# LCD-43.net
KiCad netlist of a schematic drawn in Altium Designer
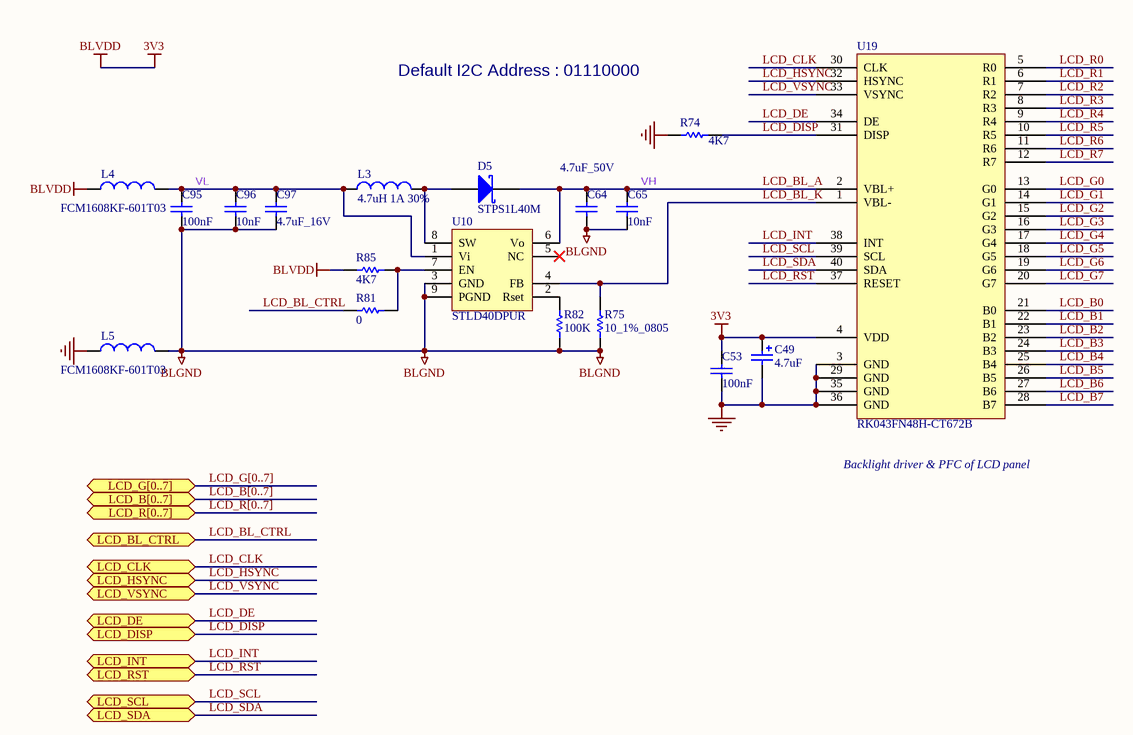
[diagram p0: LCD-43.SchDoc]

(export (version "E")
  (design (tool "Eeschema 10.0.6"))
  (components
    (comp (ref "C49")
      (value "4.7uF")
      (footprint "TAN-A")
      (description "Polarized Capacitor,4.7uF,16V,10%,typeA,AVX")
      (libsource (lib "MCD_TOOLS") (part "Cap_4.7uF_POL_10%_TANA"))
    )
    (comp (ref "C53")
      (value "100nF")
      (footprint "0402C")
      (description "Capacitor,100nF,16V,X7R,10%,0402,YAGEO")
      (libsource (lib "MCD_TOOLS") (part "Cap_100nF_X7R_10%_0402"))
    )
    (comp (ref "C64")
      (value "4.7uF_50V")
      (footprint "1206C")
      (description "Capacitor,4.7uF,50V, X7R,10%,1206,AVX")
      (libsource (lib "MCD_TOOLS") (part "Cap_4.7uF_X7R_10%_1206"))
    )
    (comp (ref "C65")
      (value "10nF")
      (footprint "0603C")
      (description "Capacitor,10nF,50V,X7R,10%,0603,YAGEO")
      (libsource (lib "MCD_TOOLS") (part "Cap_10nF_X7R_10%_0603"))
    )
    (comp (ref "C95")
      (value "100nF")
      (footprint "0603C")
      (description "Capacitor,100nF,16V,X7R,10%,0603,YAGEO")
      (libsource (lib "MCD_TOOLS") (part "Cap_100nF_X7R_10%_0603"))
    )
    (comp (ref "C96")
      (value "10nF")
      (footprint "0603C")
      (description "Capacitor,10nF,50V,X7R,10%,0603,YAGEO")
      (libsource (lib "MCD_TOOLS") (part "Cap_10nF_X7R_10%_0603"))
    )
    (comp (ref "C97")
      (value "4.7uF_16V")
      (footprint "1206C")
      (description "Capacitor,4.7uF,16V, X5R,10%,1206,AVX")
      (libsource (lib "MCD_TOOLS") (part "Cap_4.7uF_X5R_10%_1206"))
    )
    (comp (ref "D5")
      (value "STPS1L40M")
      (footprint "DO216-AA")
      (description "Low Drop power Schottky rectifier(1A, 40V, 0.4V)")
      (libsource (lib "MCD_TOOLS") (part "STPS1L40M"))
    )
    (comp (ref "L3")
      (value "4.7uH 1A 30%")
      (footprint "1210L")
      (description "FIXED IND 4.7UH 1A 180 MOHM 30% SMD")
      (libsource (lib "MCD_TOOLS") (part "Ind_4.7uH_1A_30%"))
    )
    (comp (ref "L4")
      (value "FCM1608KF-601T03")
      (footprint "0603L")
      (description "Bead,600R,350mA,0603,FCM1608KF-601T03,Tai-tech")
      (libsource (lib "MCD_TOOLS") (part "BEAD_600R_350MA_0603"))
    )
    (comp (ref "L5")
      (value "FCM1608KF-601T03")
      (footprint "0603L")
      (description "Bead,600R,350mA,0603,FCM1608KF-601T03,Tai-tech")
      (libsource (lib "MCD_TOOLS") (part "BEAD_600R_350MA_0603"))
    )
    (comp (ref "R74")
      (value "4K7")
      (footprint "0402R")
      (description "Resistor,4K7,0402,1%,YAGEO")
      (libsource (lib "MCD_TOOLS") (part "Res_4K7_1%_0402"))
    )
    (comp (ref "R75")
      (value "10_1%_0805")
      (footprint "0805R")
      (description "Resistor,10,0805,1%,Stackpole,1/4W")
      (libsource (lib "MCD_TOOLS") (part "Res_10_1%_0805"))
    )
    (comp (ref "R81")
      (value "0")
      (footprint "0402R")
      (description "Resistor,0,0402,5%,YAGEO")
      (libsource (lib "MCD_TOOLS") (part "Res_0_5%_0402"))
    )
    (comp (ref "R82")
      (value "100K")
      (footprint "0402R")
      (description "Resistor,100K,0402,1%,YAGEO")
      (libsource (lib "MCD_TOOLS") (part "Res_100K_1%_0402"))
    )
    (comp (ref "R85")
      (value "4K7")
      (footprint "0402R")
      (description "Resistor,4K7,0402,1%,YAGEO")
      (libsource (lib "MCD_TOOLS") (part "Res_4K7_1%_0402"))
    )
    (comp (ref "U10")
      (value "STLD40DPUR")
      (footprint "QFN8_0R65_3X3_ST")
      (description "White LED power supply for large display backlight, QFN8")
      (libsource (lib "MCD_TOOLS") (part "STLD40DPUR"))
    )
    (comp (ref "U19")
      (value "RK043FN48H-CT672B")
      (footprint "RK043FN48H")
      (description "4.3 inch TFT 480*272 pixels with LED Backlight and Capacitive touch panel, high luminance")
      (libsource (lib "MCD_TOOLS") (part "RK043FN48H-CT672B"))
    )
  )
  (nets
    (net (code "1") (name "/LCD_B0") (class "Default")
      (node (ref "U19") (pin "21") (pinfunction "B0_21") (pintype "passive"))
    )
    (net (code "2") (name "/LCD_B1") (class "Default")
      (node (ref "U19") (pin "22") (pinfunction "B1_22") (pintype "passive"))
    )
    (net (code "3") (name "/LCD_B2") (class "Default")
      (node (ref "U19") (pin "23") (pinfunction "B2_23") (pintype "passive"))
    )
    (net (code "4") (name "/LCD_B3") (class "Default")
      (node (ref "U19") (pin "24") (pinfunction "B3_24") (pintype "passive"))
    )
    (net (code "5") (name "/LCD_B4") (class "Default")
      (node (ref "U19") (pin "25") (pinfunction "B4_25") (pintype "passive"))
    )
    (net (code "6") (name "/LCD_B5") (class "Default")
      (node (ref "U19") (pin "26") (pinfunction "B5_26") (pintype "passive"))
    )
    (net (code "7") (name "/LCD_B6") (class "Default")
      (node (ref "U19") (pin "27") (pinfunction "B6_27") (pintype "passive"))
    )
    (net (code "8") (name "/LCD_B7") (class "Default")
      (node (ref "U19") (pin "28") (pinfunction "B7_28") (pintype "passive"))
    )
    (net (code "9") (name "/LCD_BL_A") (class "Default")
      (node (ref "C64") (pin "1") (pinfunction "1_1") (pintype "passive"))
      (node (ref "C65") (pin "2") (pinfunction "2_2") (pintype "passive"))
      (node (ref "D5") (pin "2") (pinfunction "K_2") (pintype "passive"))
      (node (ref "U10") (pin "6") (pinfunction "Vo_6") (pintype "passive"))
      (node (ref "U19") (pin "2") (pinfunction "VBL+_2") (pintype "passive"))
    )
    (net (code "10") (name "/LCD_BL_CTRL") (class "Default")
      (node (ref "R81") (pin "2") (pinfunction "2_2") (pintype "passive"))
    )
    (net (code "11") (name "/LCD_BL_K") (class "Default")
      (node (ref "R75") (pin "2") (pinfunction "2_2") (pintype "passive"))
      (node (ref "U10") (pin "4") (pinfunction "FB_4") (pintype "passive"))
      (node (ref "U19") (pin "1") (pinfunction "VBL-_1") (pintype "passive"))
    )
    (net (code "13") (name "/LCD_CLK") (class "Default")
      (node (ref "U19") (pin "30") (pinfunction "CLK_30") (pintype "passive"))
    )
    (net (code "14") (name "/LCD_DE") (class "Default")
      (node (ref "U19") (pin "34") (pinfunction "DE_34") (pintype "passive"))
    )
    (net (code "15") (name "/LCD_DISP") (class "Default")
      (node (ref "R74") (pin "1") (pinfunction "1_1") (pintype "passive"))
      (node (ref "U19") (pin "31") (pinfunction "DISP_31") (pintype "passive"))
    )
    (net (code "16") (name "/LCD_G0") (class "Default")
      (node (ref "U19") (pin "13") (pinfunction "G0_13") (pintype "passive"))
    )
    (net (code "17") (name "/LCD_G1") (class "Default")
      (node (ref "U19") (pin "14") (pinfunction "G1_14") (pintype "passive"))
    )
    (net (code "18") (name "/LCD_G2") (class "Default")
      (node (ref "U19") (pin "15") (pinfunction "G2_15") (pintype "passive"))
    )
    (net (code "19") (name "/LCD_G3") (class "Default")
      (node (ref "U19") (pin "16") (pinfunction "G3_16") (pintype "passive"))
    )
    (net (code "20") (name "/LCD_G4") (class "Default")
      (node (ref "U19") (pin "17") (pinfunction "G4_17") (pintype "passive"))
    )
    (net (code "21") (name "/LCD_G5") (class "Default")
      (node (ref "U19") (pin "18") (pinfunction "G5_18") (pintype "passive"))
    )
    (net (code "22") (name "/LCD_G6") (class "Default")
      (node (ref "U19") (pin "19") (pinfunction "G6_19") (pintype "passive"))
    )
    (net (code "23") (name "/LCD_G7") (class "Default")
      (node (ref "U19") (pin "20") (pinfunction "G7_20") (pintype "passive"))
    )
    (net (code "25") (name "/LCD_HSYNC") (class "Default")
      (node (ref "U19") (pin "32") (pinfunction "HSYNC_32") (pintype "passive"))
    )
    (net (code "26") (name "/LCD_INT") (class "Default")
      (node (ref "U19") (pin "38") (pinfunction "INT_38") (pintype "passive"))
    )
    (net (code "27") (name "/LCD_R0") (class "Default")
      (node (ref "U19") (pin "5") (pinfunction "R0_5") (pintype "passive"))
    )
    (net (code "28") (name "/LCD_R1") (class "Default")
      (node (ref "U19") (pin "6") (pinfunction "R1_6") (pintype "passive"))
    )
    (net (code "29") (name "/LCD_R2") (class "Default")
      (node (ref "U19") (pin "7") (pinfunction "R2_7") (pintype "passive"))
    )
    (net (code "30") (name "/LCD_R3") (class "Default")
      (node (ref "U19") (pin "8") (pinfunction "R3_8") (pintype "passive"))
    )
    (net (code "31") (name "/LCD_R4") (class "Default")
      (node (ref "U19") (pin "9") (pinfunction "R4_9") (pintype "passive"))
    )
    (net (code "32") (name "/LCD_R5") (class "Default")
      (node (ref "U19") (pin "10") (pinfunction "R5_10") (pintype "passive"))
    )
    (net (code "33") (name "/LCD_R6") (class "Default")
      (node (ref "U19") (pin "11") (pinfunction "R6_11") (pintype "passive"))
    )
    (net (code "34") (name "/LCD_R7") (class "Default")
      (node (ref "U19") (pin "12") (pinfunction "R7_12") (pintype "passive"))
    )
    (net (code "35") (name "/LCD_RST") (class "Default")
      (node (ref "U19") (pin "37") (pinfunction "RESET_37") (pintype "passive"))
    )
    (net (code "37") (name "/LCD_SCL") (class "Default")
      (node (ref "U19") (pin "39") (pinfunction "SCL_39") (pintype "passive"))
    )
    (net (code "38") (name "/LCD_SDA") (class "Default")
      (node (ref "U19") (pin "40") (pinfunction "SDA_40") (pintype "passive"))
    )
    (net (code "39") (name "/LCD_VSYNC") (class "Default")
      (node (ref "U19") (pin "33") (pinfunction "VSYNC_33") (pintype "passive"))
    )
    (net (code "40") (name "/VL") (class "Default")
      (node (ref "C95") (pin "2") (pinfunction "2_2") (pintype "passive"))
      (node (ref "C96") (pin "2") (pinfunction "2_2") (pintype "passive"))
      (node (ref "C97") (pin "1") (pinfunction "1_1") (pintype "passive"))
      (node (ref "L3") (pin "1") (pinfunction "1_1") (pintype "passive"))
      (node (ref "L4") (pin "2") (pinfunction "2_2") (pintype "passive"))
      (node (ref "U10") (pin "1") (pinfunction "Vi_1") (pintype "passive"))
    )
    (net (code "41") (name "3V3") (class "Default")
      (node (ref "C49") (pin "1") (pinfunction "1_1") (pintype "passive"))
      (node (ref "C53") (pin "2") (pinfunction "2_2") (pintype "passive"))
      (node (ref "L4") (pin "1") (pinfunction "1_1") (pintype "passive"))
      (node (ref "R85") (pin "2") (pinfunction "2_2") (pintype "passive"))
      (node (ref "U19") (pin "4") (pinfunction "VDD_4") (pintype "passive"))
    )
    (net (code "42") (name "BLGND") (class "Default")
      (node (ref "C64") (pin "2") (pinfunction "2_2") (pintype "passive"))
      (node (ref "C65") (pin "1") (pinfunction "1_1") (pintype "passive"))
      (node (ref "C95") (pin "1") (pinfunction "1_1") (pintype "passive"))
      (node (ref "C96") (pin "1") (pinfunction "1_1") (pintype "passive"))
      (node (ref "C97") (pin "2") (pinfunction "2_2") (pintype "passive"))
      (node (ref "L5") (pin "2") (pinfunction "2_2") (pintype "passive"))
      (node (ref "R75") (pin "1") (pinfunction "1_1") (pintype "passive"))
      (node (ref "R82") (pin "2") (pinfunction "2_2") (pintype "passive"))
      (node (ref "U10") (pin "3") (pinfunction "GND_3") (pintype "passive"))
      (node (ref "U10") (pin "9") (pinfunction "PGND_9") (pintype "passive"))
    )
    (net (code "43") (name "GND") (class "Default")
      (node (ref "C49") (pin "2") (pinfunction "2_2") (pintype "passive"))
      (node (ref "C53") (pin "1") (pinfunction "1_1") (pintype "passive"))
      (node (ref "L5") (pin "1") (pinfunction "1_1") (pintype "passive"))
      (node (ref "R74") (pin "2") (pinfunction "2_2") (pintype "passive"))
      (node (ref "U19") (pin "29") (pinfunction "GND_29") (pintype "passive"))
      (node (ref "U19") (pin "3") (pinfunction "GND_3") (pintype "passive"))
      (node (ref "U19") (pin "35") (pinfunction "GND_35") (pintype "passive"))
      (node (ref "U19") (pin "36") (pinfunction "GND_36") (pintype "passive"))
    )
    (net (code "44") (name "Net-(D5-A)") (class "Default")
      (node (ref "D5") (pin "1") (pinfunction "A_1") (pintype "passive"))
      (node (ref "L3") (pin "2") (pinfunction "2_2") (pintype "passive"))
      (node (ref "U10") (pin "8") (pinfunction "SW_8") (pintype "passive"))
    )
    (net (code "45") (name "Net-(U10-EN)") (class "Default")
      (node (ref "R81") (pin "1") (pinfunction "1_1") (pintype "passive"))
      (node (ref "R85") (pin "1") (pinfunction "1_1") (pintype "passive"))
      (node (ref "U10") (pin "7") (pinfunction "EN_7") (pintype "passive"))
    )
    (net (code "46") (name "Net-(U10-Rset)") (class "Default")
      (node (ref "R82") (pin "1") (pinfunction "1_1") (pintype "passive"))
      (node (ref "U10") (pin "2") (pinfunction "Rset_2") (pintype "passive"))
    )
    (net (code "47") (name "unconnected-(U10-NC-Pad5)") (class "Default")
      (node (ref "U10") (pin "5") (pinfunction "NC_5") (pintype "passive+no_connect"))
    )
  )
)
